# Schematic.net
KiCad netlist of a schematic drawn in Altium Designer
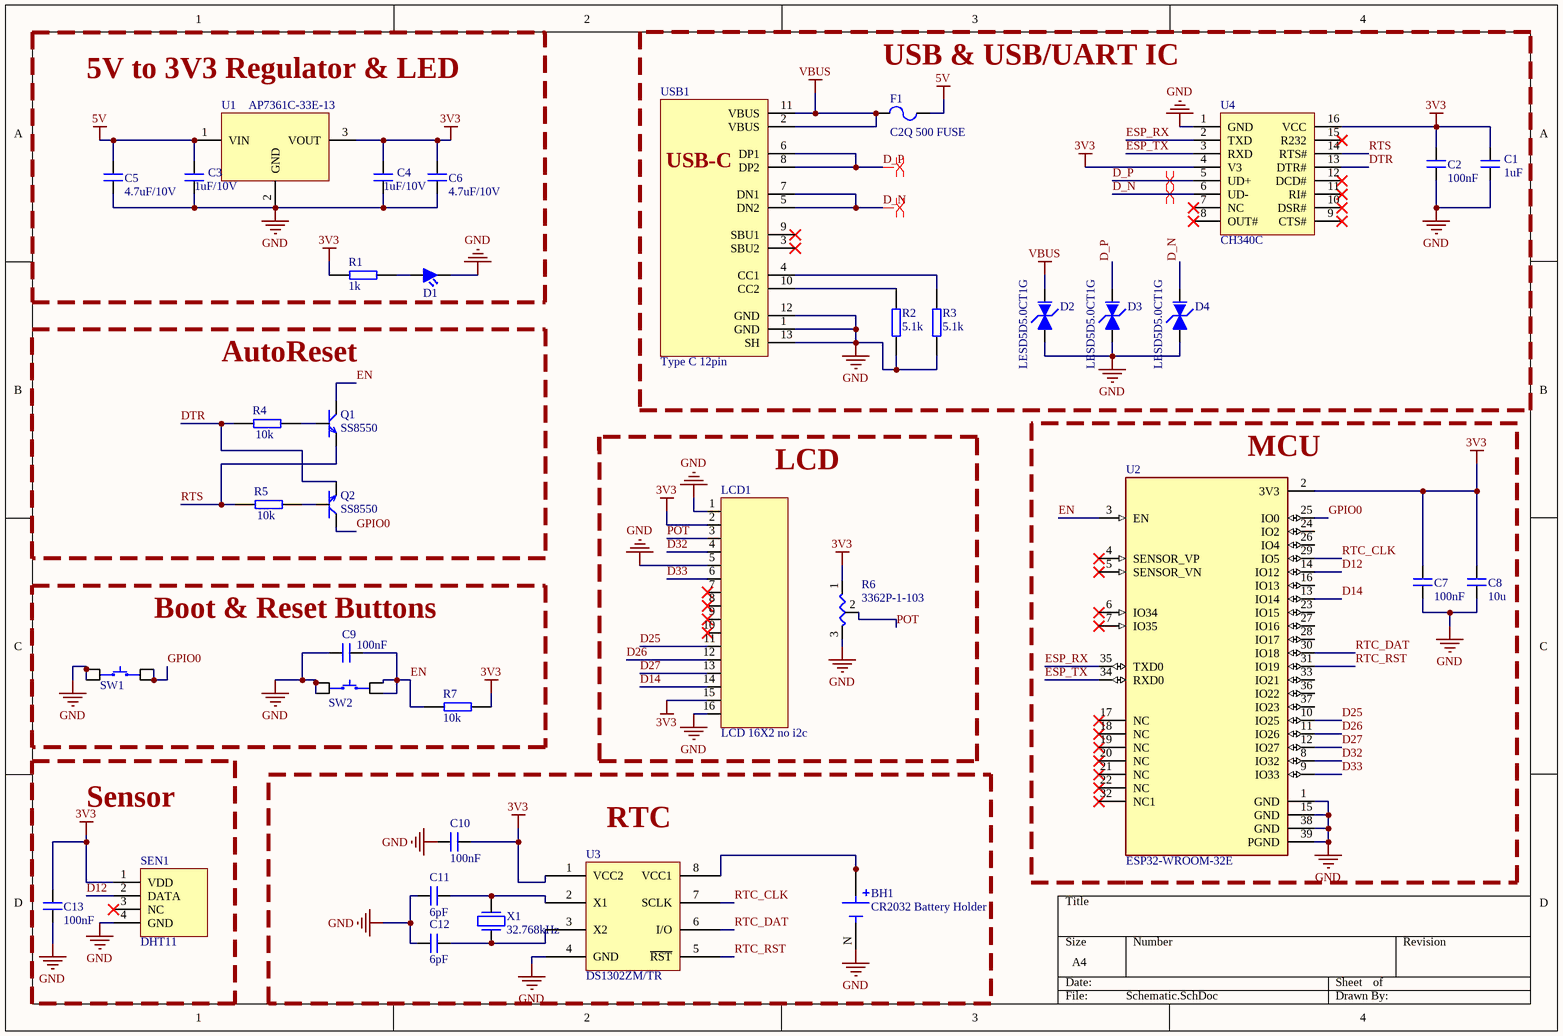
[diagram p0: Schematic.SchDoc]

(export (version "E")
  (design (tool "Eeschema 10.0.6"))
  (components
    (comp (ref "BH1")
      (value "CR2032 Battery Holder")
      (footprint "3035 battery holder CR2032")
      (description "Holder Battery; Coin Battery; 1 Cell; PC Pin; 0.787 in. Dia.")
      (fields
        (field (name "MANUFACTURER") "Keystone Electronics")
        (field (name "MANUFACTURER PART NUMBER") "3035")
      )
      (libsource (lib "GenerALI") (part "CR2032 Battery Holder"))
    )
    (comp (ref "C1")
      (value "1uF")
      (footprint "0603 CAP")
      (fields
        (field (name "MANUFACTURER") "Murata")
        (field (name "MANUFACTURER PART NUMBER") "GCM188R71E105KA64D")
      )
      (libsource (lib "GenerALI") (part "0603 1u CAP"))
    )
    (comp (ref "C2")
      (value "100nF")
      (footprint "0402 CAP")
      (fields
        (field (name "MANUFACTURER") "Murata")
        (field (name "MANUFACTURER PART NUMBER") "GRM155R71E104KE14J")
      )
      (libsource (lib "GenerALI") (part "0402 100n AP"))
    )
    (comp (ref "C3")
      (value "1uF/10V")
      (footprint "0603 CAP")
      (description "MURATA GRM155R61A475MEAAD")
      (fields
        (field (name "MANUFACTURER") "Murata")
        (field (name "MANUFACTURER PART NUMBER") "GCM188R71E105KA64D")
      )
      (libsource (lib "GenerALI") (part "0603 1u CAP"))
    )
    (comp (ref "C4")
      (value "1uF/10V")
      (footprint "0603 CAP")
      (description "MURATA GRM155R61A475MEAAD")
      (fields
        (field (name "MANUFACTURER") "Murata")
        (field (name "MANUFACTURER PART NUMBER") "GCM188R71E105KA64D")
      )
      (libsource (lib "GenerALI") (part "0603 1u CAP"))
    )
    (comp (ref "C5")
      (value "4.7uF/10V")
      (footprint "0402 CAP")
      (description "MURATA GRM155R61A475MEAAD")
      (libsource (lib "GenerALI") (part "0402 CAP"))
    )
    (comp (ref "C6")
      (value "4.7uF/10V")
      (footprint "0402 CAP")
      (description "MURATA GRM155R61A475MEAAD")
      (libsource (lib "GenerALI") (part "0402 CAP"))
    )
    (comp (ref "C7")
      (value "100nF")
      (footprint "0402 CAP")
      (fields
        (field (name "MANUFACTURER") "Murata")
        (field (name "MANUFACTURER PART NUMBER") "GRM155R71E104KE14J")
      )
      (libsource (lib "GenerALI") (part "0402 100n AP"))
    )
    (comp (ref "C8") (value "10u") (footprint "0805 CAP") (libsource (lib "GenerALI") (part "0805 10u CAP")))
    (comp (ref "C9")
      (value "100nF")
      (footprint "0402 CAP")
      (fields
        (field (name "MANUFACTURER") "Murata")
        (field (name "MANUFACTURER PART NUMBER") "GRM155R71E104KE14J")
      )
      (libsource (lib "GenerALI") (part "0402 100n AP"))
    )
    (comp (ref "C10")
      (value "100nF")
      (footprint "0402 CAP")
      (fields
        (field (name "MANUFACTURER") "Murata")
        (field (name "MANUFACTURER PART NUMBER") "GRM155R71E104KE14J")
      )
      (libsource (lib "GenerALI") (part "0402 100n AP"))
    )
    (comp (ref "C11")
      (value "6pF")
      (footprint "0402 CAP")
      (description "GRM1555C1H6R0DA01D\r\nCAP CER 6PF 50V C0G/NP0 0402")
      (libsource (lib "GenerALI") (part "0402 CAP"))
    )
    (comp (ref "C12")
      (value "6pF")
      (footprint "0402 CAP")
      (description "GRM1555C1H6R0DA01D\r\nCAP CER 6PF 50V C0G/NP0 0402")
      (libsource (lib "GenerALI") (part "0402 CAP"))
    )
    (comp (ref "C13")
      (value "100nF")
      (footprint "0402 CAP")
      (fields
        (field (name "MANUFACTURER") "Murata")
        (field (name "MANUFACTURER PART NUMBER") "GRM155R71E104KE14J")
      )
      (libsource (lib "GenerALI") (part "0402 100n AP"))
    )
    (comp (ref "D1")
      (value "LED RED 0805")
      (footprint "LED 0805")
      (libsource (lib "GenerALI") (part "LED RED 0805"))
    )
    (comp (ref "D2")
      (value "LESD5D5.0CT1G")
      (footprint "SC-79/SOD-523")
      (description "TVS Diode")
      (libsource (lib "GenerALI") (part "LESD5D5.0CT1G"))
    )
    (comp (ref "D3")
      (value "LESD5D5.0CT1G")
      (footprint "SC-79/SOD-523")
      (description "TVS Diode")
      (libsource (lib "GenerALI") (part "LESD5D5.0CT1G"))
    )
    (comp (ref "D4")
      (value "LESD5D5.0CT1G")
      (footprint "SC-79/SOD-523")
      (description "TVS Diode")
      (libsource (lib "GenerALI") (part "LESD5D5.0CT1G"))
    )
    (comp (ref "F1")
      (value "C2Q 500 FUSE")
      (footprint "C2Q 500 0603")
      (description "Fuse Chip Very Fast Acting 0.5A 32V SMD Solder Pad 0603 Ceramic CE/UL")
      (fields (field (name "MANUFACTURER") "Bel") (field (name "MANUFACTURER PART NUMBER") "C2Q500"))
      (libsource (lib "GenerALI") (part "C2Q 500 FUSE"))
    )
    (comp (ref "LCD1")
      (value "LCD 16X2 no i2c")
      (footprint "LCD 16X2 NO I2C")
      (libsource (lib "GenerALI") (part "LCD 16X2 no i2c"))
    )
    (comp (ref "Q1")
      (value "SS8550")
      (footprint "SOT23")
      (description "Bjt Transistor NPN 25V 1.5A 300MW 3-PIN SOT-23 T/r")
      (fields (field (name "MANUFACTURER") "Comchip") (field (name "MANUFACTURER PART NUMBER") "SS8050-G"))
      (libsource (lib "GenerALI") (part "SS8550"))
    )
    (comp (ref "Q2")
      (value "SS8550")
      (footprint "SOT23")
      (description "Bjt Transistor NPN 25V 1.5A 300MW 3-PIN SOT-23 T/r")
      (fields (field (name "MANUFACTURER") "Comchip") (field (name "MANUFACTURER PART NUMBER") "SS8050-G"))
      (libsource (lib "GenerALI") (part "SS8550"))
    )
    (comp (ref "R1")
      (value "1k")
      (footprint "0402 RES")
      (fields
        (field (name "MANUFACTURER") "Samsung")
        (field (name "MANUFACTURER PART NUMBER") "RC1005F103CS")
        (field (name "TOLERANCE") "1%")
      )
      (libsource (lib "GenerALI") (part "0402 1k RES"))
    )
    (comp (ref "R2") (value "5.1k") (footprint "0402 RES") (libsource (lib "GenerALI") (part "0402 RES")))
    (comp (ref "R3") (value "5.1k") (footprint "0402 RES") (libsource (lib "GenerALI") (part "0402 RES")))
    (comp (ref "R4")
      (value "10k")
      (footprint "0402 RES")
      (fields
        (field (name "MANUFACTURER") "Samsung")
        (field (name "MANUFACTURER PART NUMBER") "RC1005F103CS")
        (field (name "TOLERANCE") "1%")
      )
      (libsource (lib "GenerALI") (part "0402 10k RES"))
    )
    (comp (ref "R5")
      (value "10k")
      (footprint "0402 RES")
      (fields
        (field (name "MANUFACTURER") "Samsung")
        (field (name "MANUFACTURER PART NUMBER") "RC1005F103CS")
        (field (name "TOLERANCE") "1%")
      )
      (libsource (lib "GenerALI") (part "0402 10k RES"))
    )
    (comp (ref "R6")
      (value "3362P-1-103")
      (footprint "3362P-1-103")
      (description "Trimmer, Cermet, 0.5W, 10000ohm, 10% +/-Tol, -100,100ppm/Cel, 2628")
      (fields
        (field (name "MANUFACTURER") "Bourns")
        (field (name "MANUFACTURER PART NUMBER") "3362P-1-103RLF")
      )
      (libsource (lib "GenerALI") (part "3362P-1-103"))
    )
    (comp (ref "R7")
      (value "10k")
      (footprint "0402 RES")
      (fields
        (field (name "MANUFACTURER") "Samsung")
        (field (name "MANUFACTURER PART NUMBER") "RC1005F103CS")
        (field (name "TOLERANCE") "1%")
      )
      (libsource (lib "GenerALI") (part "0402 10k RES"))
    )
    (comp (ref "SEN1")
      (value "DHT11")
      (footprint "DHT11")
      (description "Temperature and Humidity Sensor")
      (fields (field (name "VOLTAGE") "3 to 5"))
      (libsource (lib "GenerALI") (part "DHT11"))
    )
    (comp (ref "SW1")
      (value "SWITCH TACTILE")
      (footprint "4 pin tactile switch")
      (fields
        (field (name "MANUFACTURER") "E-Switch")
        (field (name "MANUFACTURER PART NUMBER") "TL3305BF260QG")
      )
      (libsource (lib "GenerALI") (part "SWITCH TACTILE"))
    )
    (comp (ref "SW2")
      (value "SWITCH TACTILE")
      (footprint "4 pin tactile switch")
      (fields
        (field (name "MANUFACTURER") "E-Switch")
        (field (name "MANUFACTURER PART NUMBER") "TL3305BF260QG")
      )
      (libsource (lib "GenerALI") (part "SWITCH TACTILE"))
    )
    (comp (ref "U1")
      (value "AP7361C-33E-13")
      (footprint "SOT223")
      (description "Fixed Positive LDO Regulator, 3.3V, 0.15V Dropout, SOT223")
      (fields (field (name "MANUFACTURER") "Diodes"))
      (libsource (lib "GenerALI") (part "AP7361C-33E-13"))
    )
    (comp (ref "U2")
      (value "ESP32-WROOM-32E")
      (footprint "ESP32-WROOM-32E")
      (libsource (lib "GenerALI") (part "ESP32-WROOM-32E"))
    )
    (comp (ref "U3")
      (value "DS1302ZM/TR")
      (footprint "SOP-8")
      (description "RTC IC SOP-8 Real-Time Clocks(RTC) ROHS")
      (fields (field (name "MANUFACTURER") "HGSEMI") (field (name "JLCPCB PART") "C910859"))
      (libsource (lib "GenerALI") (part "DS1302ZM/TR"))
    )
    (comp (ref "U4")
      (value "CH340C")
      (footprint "SOP-16")
      (description "USB to UART bridge IC\r\nNo Crystal needed")
      (fields (field (name "JLCPCB PART") "C7464026"))
      (libsource (lib "GenerALI") (part "CH340C"))
    )
    (comp (ref "USB1")
      (value "Type C 12pin")
      (footprint "TYPE-C 16PIN 2MD(073)")
      (description "Manufacturer SHOU HAN\r\nMFR.Part #TYPE-C 16PIN 2MD(073)\r\nJLCPCB Part # C2765186")
      (fields (field (name "MANUFACTURER") "SHOU HAN") (field (name "JLCPCB PART") "C2765186"))
      (libsource (lib "GenerALI") (part "USB TYPE C 12 PIN (Right Angle)"))
    )
    (comp (ref "X1")
      (value "32.768kHz")
      (footprint "SMD3215-2P")
      (description "32.768kHz Surface mount crystal oscillator 6pF ±20ppm SMD3215-2P Crystals ROHS")
      (fields (field (name "JLCPCB PART") "C95361"))
      (libsource (lib "GenerALI") (part "Q13FC13500049"))
    )
  )
  (nets
    (net (code "1") (name "/D12") (class "Default")
      (node (ref "SEN1") (pin "2") (pinfunction "DATA_2") (pintype "passive"))
      (node (ref "U2") (pin "14") (pinfunction "IO12_14") (pintype "bidirectional"))
    )
    (net (code "2") (name "/D14") (class "Default")
      (node (ref "LCD1") (pin "14") (pinfunction "14_14") (pintype "passive"))
      (node (ref "U2") (pin "13") (pinfunction "IO14_13") (pintype "bidirectional"))
    )
    (net (code "3") (name "/D25") (class "Default")
      (node (ref "LCD1") (pin "11") (pinfunction "11_11") (pintype "passive"))
      (node (ref "U2") (pin "10") (pinfunction "IO25_10") (pintype "bidirectional"))
    )
    (net (code "4") (name "/D26") (class "Default")
      (node (ref "LCD1") (pin "12") (pinfunction "12_12") (pintype "passive"))
      (node (ref "U2") (pin "11") (pinfunction "IO26_11") (pintype "bidirectional"))
    )
    (net (code "5") (name "/D27") (class "Default")
      (node (ref "LCD1") (pin "13") (pinfunction "13_13") (pintype "passive"))
      (node (ref "U2") (pin "12") (pinfunction "IO27_12") (pintype "bidirectional"))
    )
    (net (code "6") (name "/D32") (class "Default")
      (node (ref "LCD1") (pin "4") (pinfunction "4_4") (pintype "passive"))
      (node (ref "U2") (pin "8") (pinfunction "IO32_8") (pintype "bidirectional"))
    )
    (net (code "7") (name "/D33") (class "Default")
      (node (ref "LCD1") (pin "6") (pinfunction "6_6") (pintype "passive"))
      (node (ref "U2") (pin "9") (pinfunction "IO33_9") (pintype "bidirectional"))
    )
    (net (code "8") (name "/DTR") (class "Default")
      (node (ref "Q2") (pin "2") (pinfunction "E_2") (pintype "passive"))
      (node (ref "R4") (pin "1") (pinfunction "1_1") (pintype "passive"))
      (node (ref "U4") (pin "13") (pinfunction "DTR#_13") (pintype "passive"))
    )
    (net (code "9") (name "/D_N") (class "Default")
      (node (ref "D4") (pin "1") (pinfunction "1_1") (pintype "passive"))
      (node (ref "U4") (pin "6") (pinfunction "UD-_6") (pintype "passive"))
      (node (ref "USB1") (pin "5") (pinfunction "DN2_5") (pintype "passive"))
      (node (ref "USB1") (pin "7") (pinfunction "DN1_7") (pintype "passive"))
    )
    (net (code "10") (name "/D_P") (class "Default")
      (node (ref "D3") (pin "1") (pinfunction "1_1") (pintype "passive"))
      (node (ref "U4") (pin "5") (pinfunction "UD+_5") (pintype "passive"))
      (node (ref "USB1") (pin "6") (pinfunction "DP1_6") (pintype "passive"))
      (node (ref "USB1") (pin "8") (pinfunction "DP2_8") (pintype "passive"))
    )
    (net (code "11") (name "/EN") (class "Default")
      (node (ref "C9") (pin "2") (pinfunction "2_2") (pintype "passive"))
      (node (ref "Q1") (pin "3") (pinfunction "C_3") (pintype "passive"))
      (node (ref "R7") (pin "2") (pinfunction "2_2") (pintype "passive"))
      (node (ref "SW2") (pin "2") (pinfunction "2_2") (pintype "passive"))
      (node (ref "SW2") (pin "4") (pinfunction "4_4") (pintype "passive"))
      (node (ref "U2") (pin "3") (pinfunction "EN_3") (pintype "input"))
    )
    (net (code "12") (name "/ESP_RX") (class "Default")
      (node (ref "U2") (pin "35") (pinfunction "TXD0_35") (pintype "bidirectional"))
      (node (ref "U4") (pin "2") (pinfunction "TXD_2") (pintype "passive"))
    )
    (net (code "13") (name "/ESP_TX") (class "Default")
      (node (ref "U2") (pin "34") (pinfunction "RXD0_34") (pintype "bidirectional"))
      (node (ref "U4") (pin "3") (pinfunction "RXD_3") (pintype "passive"))
    )
    (net (code "14") (name "/GPIO0") (class "Default")
      (node (ref "Q2") (pin "3") (pinfunction "C_3") (pintype "passive"))
      (node (ref "SW1") (pin "2") (pinfunction "2_2") (pintype "passive"))
      (node (ref "SW1") (pin "4") (pinfunction "4_4") (pintype "passive"))
      (node (ref "U2") (pin "25") (pinfunction "IO0_25") (pintype "bidirectional"))
    )
    (net (code "15") (name "/POT") (class "Default")
      (node (ref "LCD1") (pin "3") (pinfunction "3_3") (pintype "passive"))
      (node (ref "R6") (pin "2") (pinfunction "2_2") (pintype "passive"))
    )
    (net (code "16") (name "/RTC_CLK") (class "Default")
      (node (ref "U2") (pin "29") (pinfunction "IO5_29") (pintype "bidirectional"))
      (node (ref "U3") (pin "7") (pinfunction "SCLK_7") (pintype "passive"))
    )
    (net (code "17") (name "/RTC_DAT") (class "Default")
      (node (ref "U2") (pin "30") (pinfunction "IO18_30") (pintype "bidirectional"))
      (node (ref "U3") (pin "6") (pinfunction "I/O_6") (pintype "passive"))
    )
    (net (code "18") (name "/RTC_RST") (class "Default")
      (node (ref "U2") (pin "31") (pinfunction "IO19_31") (pintype "bidirectional"))
      (node (ref "U3") (pin "5") (pinfunction "~{RST}_5") (pintype "passive"))
    )
    (net (code "19") (name "/RTS") (class "Default")
      (node (ref "Q1") (pin "2") (pinfunction "E_2") (pintype "passive"))
      (node (ref "R5") (pin "1") (pinfunction "1_1") (pintype "passive"))
      (node (ref "U4") (pin "14") (pinfunction "RTS#_14") (pintype "passive"))
    )
    (net (code "20") (name "3V3") (class "Default")
      (node (ref "C1") (pin "2") (pinfunction "2_2") (pintype "passive"))
      (node (ref "C10") (pin "2") (pinfunction "2_2") (pintype "passive"))
      (node (ref "C13") (pin "2") (pinfunction "2_2") (pintype "passive"))
      (node (ref "C2") (pin "2") (pinfunction "2_2") (pintype "passive"))
      (node (ref "C4") (pin "2") (pinfunction "2_2") (pintype "passive"))
      (node (ref "C6") (pin "2") (pinfunction "2_2") (pintype "passive"))
      (node (ref "C7") (pin "2") (pinfunction "2_2") (pintype "passive"))
      (node (ref "C8") (pin "2") (pinfunction "2_2") (pintype "passive"))
      (node (ref "LCD1") (pin "15") (pinfunction "15_15") (pintype "passive"))
      (node (ref "LCD1") (pin "2") (pinfunction "2_2") (pintype "passive"))
      (node (ref "R1") (pin "1") (pinfunction "1_1") (pintype "passive"))
      (node (ref "R6") (pin "1") (pinfunction "1_1") (pintype "passive"))
      (node (ref "R7") (pin "1") (pinfunction "1_1") (pintype "passive"))
      (node (ref "SEN1") (pin "1") (pinfunction "VDD_1") (pintype "passive"))
      (node (ref "U1") (pin "3") (pinfunction "VOUT_3") (pintype "passive"))
      (node (ref "U2") (pin "2") (pinfunction "3V3_2") (pintype "power_in"))
      (node (ref "U3") (pin "1") (pinfunction "VCC2_1") (pintype "passive"))
      (node (ref "U4") (pin "16") (pinfunction "VCC_16") (pintype "passive"))
      (node (ref "U4") (pin "4") (pinfunction "V3_4") (pintype "passive"))
    )
    (net (code "21") (name "5V") (class "Default")
      (node (ref "C3") (pin "2") (pinfunction "2_2") (pintype "passive"))
      (node (ref "C5") (pin "2") (pinfunction "2_2") (pintype "passive"))
      (node (ref "F1") (pin "2") (pinfunction "2_2") (pintype "passive"))
      (node (ref "U1") (pin "1") (pinfunction "VIN_1") (pintype "passive"))
    )
    (net (code "22") (name "GND") (class "Default")
      (node (ref "BH1") (pin "N") (pinfunction "NEG_N") (pintype "passive"))
      (node (ref "C1") (pin "1") (pinfunction "1_1") (pintype "passive"))
      (node (ref "C10") (pin "1") (pinfunction "1_1") (pintype "passive"))
      (node (ref "C11") (pin "2") (pinfunction "2_2") (pintype "passive"))
      (node (ref "C12") (pin "2") (pinfunction "2_2") (pintype "passive"))
      (node (ref "C13") (pin "1") (pinfunction "1_1") (pintype "passive"))
      (node (ref "C2") (pin "1") (pinfunction "1_1") (pintype "passive"))
      (node (ref "C3") (pin "1") (pinfunction "1_1") (pintype "passive"))
      (node (ref "C4") (pin "1") (pinfunction "1_1") (pintype "passive"))
      (node (ref "C5") (pin "1") (pinfunction "1_1") (pintype "passive"))
      (node (ref "C6") (pin "1") (pinfunction "1_1") (pintype "passive"))
      (node (ref "C7") (pin "1") (pinfunction "1_1") (pintype "passive"))
      (node (ref "C8") (pin "1") (pinfunction "1_1") (pintype "passive"))
      (node (ref "C9") (pin "1") (pinfunction "1_1") (pintype "passive"))
      (node (ref "D1") (pin "1") (pinfunction "1_1") (pintype "passive"))
      (node (ref "D2") (pin "2") (pinfunction "2_2") (pintype "passive"))
      (node (ref "D3") (pin "2") (pinfunction "2_2") (pintype "passive"))
      (node (ref "D4") (pin "2") (pinfunction "2_2") (pintype "passive"))
      (node (ref "LCD1") (pin "1") (pinfunction "1_1") (pintype "passive"))
      (node (ref "LCD1") (pin "16") (pinfunction "16_16") (pintype "passive"))
      (node (ref "LCD1") (pin "5") (pinfunction "5_5") (pintype "passive"))
      (node (ref "R2") (pin "1") (pinfunction "1_1") (pintype "passive"))
      (node (ref "R3") (pin "1") (pinfunction "1_1") (pintype "passive"))
      (node (ref "R6") (pin "3") (pinfunction "3_3") (pintype "passive"))
      (node (ref "SEN1") (pin "4") (pinfunction "GND_4") (pintype "passive"))
      (node (ref "SW1") (pin "1") (pinfunction "1_1") (pintype "passive"))
      (node (ref "SW1") (pin "3") (pinfunction "3_3") (pintype "passive"))
      (node (ref "SW2") (pin "1") (pinfunction "1_1") (pintype "passive"))
      (node (ref "SW2") (pin "3") (pinfunction "3_3") (pintype "passive"))
      (node (ref "U1") (pin "2") (pinfunction "GND_2") (pintype "passive"))
      (node (ref "U2") (pin "1") (pinfunction "GND_1") (pintype "power_in"))
      (node (ref "U2") (pin "15") (pinfunction "GND_15") (pintype "power_in"))
      (node (ref "U2") (pin "38") (pinfunction "GND_38") (pintype "power_in"))
      (node (ref "U2") (pin "39") (pinfunction "PGND_39") (pintype "power_in"))
      (node (ref "U3") (pin "4") (pinfunction "GND_4") (pintype "passive"))
      (node (ref "U4") (pin "1") (pinfunction "GND_1") (pintype "passive"))
      (node (ref "USB1") (pin "1") (pinfunction "GND_1") (pintype "passive"))
      (node (ref "USB1") (pin "12") (pinfunction "GND_12") (pintype "passive"))
      (node (ref "USB1") (pin "13") (pinfunction "SH_13") (pintype "passive"))
    )
    (net (code "23") (name "Net-(BH1-POS)") (class "Default")
      (node (ref "BH1") (pin "P") (pinfunction "POS_P") (pintype "passive"))
      (node (ref "U3") (pin "8") (pinfunction "VCC1_8") (pintype "passive"))
    )
    (net (code "24") (name "Net-(D1-Pad2)") (class "Default")
      (node (ref "D1") (pin "2") (pinfunction "2_2") (pintype "passive"))
      (node (ref "R1") (pin "2") (pinfunction "2_2") (pintype "passive"))
    )
    (net (code "25") (name "Net-(Q1-B)") (class "Default")
      (node (ref "Q1") (pin "1") (pinfunction "B_1") (pintype "passive"))
      (node (ref "R4") (pin "2") (pinfunction "2_2") (pintype "passive"))
    )
    (net (code "26") (name "Net-(Q2-B)") (class "Default")
      (node (ref "Q2") (pin "1") (pinfunction "B_1") (pintype "passive"))
      (node (ref "R5") (pin "2") (pinfunction "2_2") (pintype "passive"))
    )
    (net (code "27") (name "Net-(U3-X1)") (class "Default")
      (node (ref "C11") (pin "1") (pinfunction "1_1") (pintype "passive"))
      (node (ref "U3") (pin "2") (pinfunction "X1_2") (pintype "passive"))
      (node (ref "X1") (pin "2") (pinfunction "2_2") (pintype "passive"))
    )
    (net (code "28") (name "Net-(U3-X2)") (class "Default")
      (node (ref "C12") (pin "1") (pinfunction "1_1") (pintype "passive"))
      (node (ref "U3") (pin "3") (pinfunction "X2_3") (pintype "passive"))
      (node (ref "X1") (pin "1") (pinfunction "1_1") (pintype "passive"))
    )
    (net (code "29") (name "Net-(USB1-CC1)") (class "Default")
      (node (ref "R3") (pin "2") (pinfunction "2_2") (pintype "passive"))
      (node (ref "USB1") (pin "4") (pinfunction "CC1_4") (pintype "passive"))
    )
    (net (code "30") (name "Net-(USB1-CC2)") (class "Default")
      (node (ref "R2") (pin "2") (pinfunction "2_2") (pintype "passive"))
      (node (ref "USB1") (pin "10") (pinfunction "CC2_10") (pintype "passive"))
    )
    (net (code "31") (name "VBUS") (class "Default")
      (node (ref "D2") (pin "1") (pinfunction "1_1") (pintype "passive"))
      (node (ref "F1") (pin "1") (pinfunction "1_1") (pintype "passive"))
      (node (ref "USB1") (pin "11") (pinfunction "VBUS_11") (pintype "passive"))
      (node (ref "USB1") (pin "2") (pinfunction "VBUS_2") (pintype "passive"))
    )
    (net (code "32") (name "unconnected-(LCD1-Pad7)") (class "Default")
      (node (ref "LCD1") (pin "7") (pinfunction "7_7") (pintype "passive+no_connect"))
    )
    (net (code "33") (name "unconnected-(LCD1-Pad8)") (class "Default")
      (node (ref "LCD1") (pin "8") (pinfunction "8_8") (pintype "passive+no_connect"))
    )
    (net (code "34") (name "unconnected-(LCD1-Pad9)") (class "Default")
      (node (ref "LCD1") (pin "9") (pinfunction "9_9") (pintype "passive+no_connect"))
    )
    (net (code "35") (name "unconnected-(LCD1-Pad10)") (class "Default")
      (node (ref "LCD1") (pin "10") (pinfunction "10_10") (pintype "passive+no_connect"))
    )
    (net (code "36") (name "unconnected-(SEN1-NC-Pad3)") (class "Default")
      (node (ref "SEN1") (pin "3") (pinfunction "NC_3") (pintype "passive+no_connect"))
    )
    (net (code "37") (name "unconnected-(U2-IO2-Pad24)") (class "Default")
      (node (ref "U2") (pin "24") (pinfunction "IO2_24") (pintype "bidirectional"))
    )
    (net (code "38") (name "unconnected-(U2-IO4-Pad26)") (class "Default")
      (node (ref "U2") (pin "26") (pinfunction "IO4_26") (pintype "bidirectional"))
    )
    (net (code "39") (name "unconnected-(U2-IO13-Pad16)") (class "Default")
      (node (ref "U2") (pin "16") (pinfunction "IO13_16") (pintype "bidirectional"))
    )
    (net (code "40") (name "unconnected-(U2-IO15-Pad23)") (class "Default")
      (node (ref "U2") (pin "23") (pinfunction "IO15_23") (pintype "bidirectional"))
    )
    (net (code "41") (name "unconnected-(U2-IO16-Pad27)") (class "Default")
      (node (ref "U2") (pin "27") (pinfunction "IO16_27") (pintype "bidirectional"))
    )
    (net (code "42") (name "unconnected-(U2-IO17-Pad28)") (class "Default")
      (node (ref "U2") (pin "28") (pinfunction "IO17_28") (pintype "bidirectional"))
    )
    (net (code "43") (name "unconnected-(U2-IO21-Pad33)") (class "Default")
      (node (ref "U2") (pin "33") (pinfunction "IO21_33") (pintype "bidirectional"))
    )
    (net (code "44") (name "unconnected-(U2-IO22-Pad36)") (class "Default")
      (node (ref "U2") (pin "36") (pinfunction "IO22_36") (pintype "bidirectional"))
    )
    (net (code "45") (name "unconnected-(U2-IO23-Pad37)") (class "Default")
      (node (ref "U2") (pin "37") (pinfunction "IO23_37") (pintype "bidirectional"))
    )
    (net (code "46") (name "unconnected-(U2-IO34-Pad6)") (class "Default")
      (node (ref "U2") (pin "6") (pinfunction "IO34_6") (pintype "input+no_connect"))
    )
    (net (code "47") (name "unconnected-(U2-IO35-Pad7)") (class "Default")
      (node (ref "U2") (pin "7") (pinfunction "IO35_7") (pintype "input+no_connect"))
    )
    (net (code "48") (name "unconnected-(U2-NC-Pad17)") (class "Default")
      (node (ref "U2") (pin "17") (pinfunction "NC_17") (pintype "passive+no_connect"))
    )
    (net (code "49") (name "unconnected-(U2-NC-Pad18)") (class "Default")
      (node (ref "U2") (pin "18") (pinfunction "NC_18") (pintype "passive+no_connect"))
    )
    (net (code "50") (name "unconnected-(U2-NC-Pad19)") (class "Default")
      (node (ref "U2") (pin "19") (pinfunction "NC_19") (pintype "passive+no_connect"))
    )
    (net (code "51") (name "unconnected-(U2-NC-Pad20)") (class "Default")
      (node (ref "U2") (pin "20") (pinfunction "NC_20") (pintype "passive+no_connect"))
    )
    (net (code "52") (name "unconnected-(U2-NC-Pad21)") (class "Default")
      (node (ref "U2") (pin "21") (pinfunction "NC_21") (pintype "passive+no_connect"))
    )
    (net (code "53") (name "unconnected-(U2-NC-Pad22)") (class "Default")
      (node (ref "U2") (pin "22") (pinfunction "NC_22") (pintype "passive+no_connect"))
    )
    (net (code "54") (name "unconnected-(U2-NC1-Pad32)") (class "Default")
      (node (ref "U2") (pin "32") (pinfunction "NC1_32") (pintype "passive+no_connect"))
    )
    (net (code "55") (name "unconnected-(U2-SENSOR_VN-Pad5)") (class "Default")
      (node (ref "U2") (pin "5") (pinfunction "SENSOR_VN_5") (pintype "input+no_connect"))
    )
    (net (code "56") (name "unconnected-(U2-SENSOR_VP-Pad4)") (class "Default")
      (node (ref "U2") (pin "4") (pinfunction "SENSOR_VP_4") (pintype "input+no_connect"))
    )
    (net (code "57") (name "unconnected-(U4-CTS#-Pad9)") (class "Default")
      (node (ref "U4") (pin "9") (pinfunction "CTS#_9") (pintype "passive+no_connect"))
    )
    (net (code "58") (name "unconnected-(U4-DCD#-Pad12)") (class "Default")
      (node (ref "U4") (pin "12") (pinfunction "DCD#_12") (pintype "passive+no_connect"))
    )
    (net (code "59") (name "unconnected-(U4-DSR#-Pad10)") (class "Default")
      (node (ref "U4") (pin "10") (pinfunction "DSR#_10") (pintype "passive+no_connect"))
    )
    (net (code "60") (name "unconnected-(U4-NC-Pad7)") (class "Default")
      (node (ref "U4") (pin "7") (pinfunction "NC_7") (pintype "passive+no_connect"))
    )
    (net (code "61") (name "unconnected-(U4-OUT#-Pad8)") (class "Default")
      (node (ref "U4") (pin "8") (pinfunction "OUT#_8") (pintype "passive+no_connect"))
    )
    (net (code "62") (name "unconnected-(U4-R232-Pad15)") (class "Default")
      (node (ref "U4") (pin "15") (pinfunction "R232_15") (pintype "passive+no_connect"))
    )
    (net (code "63") (name "unconnected-(U4-RI#-Pad11)") (class "Default")
      (node (ref "U4") (pin "11") (pinfunction "RI#_11") (pintype "passive+no_connect"))
    )
    (net (code "64") (name "unconnected-(USB1-SBU1-Pad9)") (class "Default")
      (node (ref "USB1") (pin "9") (pinfunction "SBU1_9") (pintype "passive+no_connect"))
    )
    (net (code "65") (name "unconnected-(USB1-SBU2-Pad3)") (class "Default")
      (node (ref "USB1") (pin "3") (pinfunction "SBU2_3") (pintype "passive+no_connect"))
    )
  )
)
